# RELAY13.net
KiCad netlist of a schematic drawn in Altium Designer
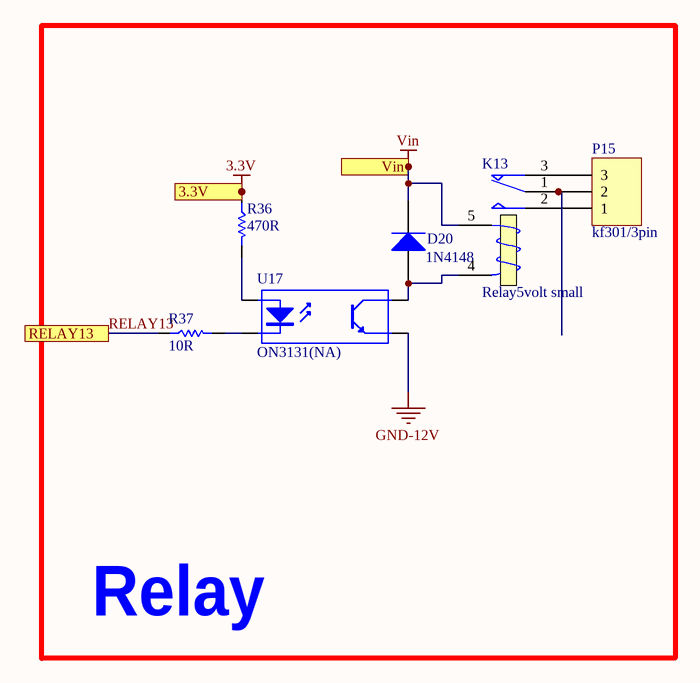
[diagram p0: RELAY13.SchDoc]

(export (version "E")
  (design (tool "Eeschema 10.0.6"))
  (components
    (comp (ref "D20")
      (value "1N4148")
      (footprint "sod123")
      (description "1 Amp General Purpose Rectifier")
      (fields (field (name "PUBLISHER") "Altium Limited"))
      (libsource (lib "Miscellaneous Devices") (part "Diode 1N4007"))
    )
    (comp (ref "K13")
      (value "Relay5volt small")
      (footprint "relay5_childern")
      (description "SPDT Relay")
      (fields (field (name "PUBLISHER") "Altium Limited"))
      (libsource (lib "FLIB") (part "Relay"))
    )
    (comp (ref "P15")
      (value "kf301/3pin")
      (footprint "Blue Connector 1*3 -kf301")
      (fields (field (name "PUBLISHER") "Altium Limited"))
      (libsource (lib "Miscellaneous Connectors") (part "Header 3"))
    )
    (comp (ref "R36")
      (value "470R")
      (footprint "0805/resistor")
      (description "Resistor")
      (fields (field (name "TOLERANCE") "5%") (field (name "POWER") "1/8 W"))
      (libsource (lib "skille") (part "Resistor"))
    )
    (comp (ref "R37")
      (value "10R")
      (footprint "0805/resistor")
      (description "Resistor")
      (fields (field (name "TOLERANCE") "5%") (field (name "POWER") "1/8 W"))
      (libsource (lib "skille") (part "Resistor"))
    )
    (comp (ref "U17")
      (value "ON3131(NA)")
      (footprint "OPTO_COUPLER")
      (description "4-Pin Phototransistor Optocoupler")
      (fields (field (name "PUBLISHER") "Altium Limited"))
      (libsource (lib "skille") (part "Optoisolator1"))
    )
  )
  (nets
    (net (code "1") (name "/RELAY13") (class "Default")
      (node (ref "R37") (pin "1") (pinfunction "1_1") (pintype "passive"))
    )
    (net (code "2") (name "3.3V") (class "Default")
      (node (ref "R36") (pin "1") (pinfunction "1_1") (pintype "passive"))
    )
    (net (code "3") (name "GND-12V") (class "Default")
      (node (ref "U17") (pin "3") (pinfunction "E_3") (pintype "passive"))
    )
    (net (code "4") (name "Net-(K13-COM)") (class "Default")
      (node (ref "K13") (pin "1") (pinfunction "COM_1") (pintype "passive"))
      (node (ref "P15") (pin "2") (pinfunction "2_2") (pintype "passive"))
    )
    (net (code "5") (name "Net-(K13-NO)") (class "Default")
      (node (ref "K13") (pin "2") (pinfunction "NO_2") (pintype "passive"))
      (node (ref "P15") (pin "1") (pinfunction "1_1") (pintype "passive"))
    )
    (net (code "6") (name "Net-(K13-T1)") (class "Default")
      (node (ref "K13") (pin "3") (pinfunction "T1_3") (pintype "passive"))
      (node (ref "P15") (pin "3") (pinfunction "3_3") (pintype "passive"))
    )
    (net (code "7") (name "Net-(K13-T2)") (class "Default")
      (node (ref "D20") (pin "A") (pinfunction "A_A") (pintype "passive"))
      (node (ref "K13") (pin "4") (pinfunction "T2_4") (pintype "passive"))
      (node (ref "U17") (pin "4") (pinfunction "C_4") (pintype "passive"))
    )
    (net (code "8") (name "Net-(U17-A)") (class "Default")
      (node (ref "R36") (pin "2") (pinfunction "2_2") (pintype "passive"))
      (node (ref "U17") (pin "1") (pinfunction "A_1") (pintype "passive"))
    )
    (net (code "9") (name "Net-(U17-K)") (class "Default")
      (node (ref "R37") (pin "2") (pinfunction "2_2") (pintype "passive"))
      (node (ref "U17") (pin "2") (pinfunction "K_2") (pintype "passive"))
    )
    (net (code "10") (name "Vin") (class "Default")
      (node (ref "D20") (pin "K") (pinfunction "K_K") (pintype "passive"))
      (node (ref "K13") (pin "5") (pinfunction "5_5") (pintype "passive"))
    )
  )
)
